# SCH.net
KiCad netlist of a schematic drawn in EasyEDA Pro
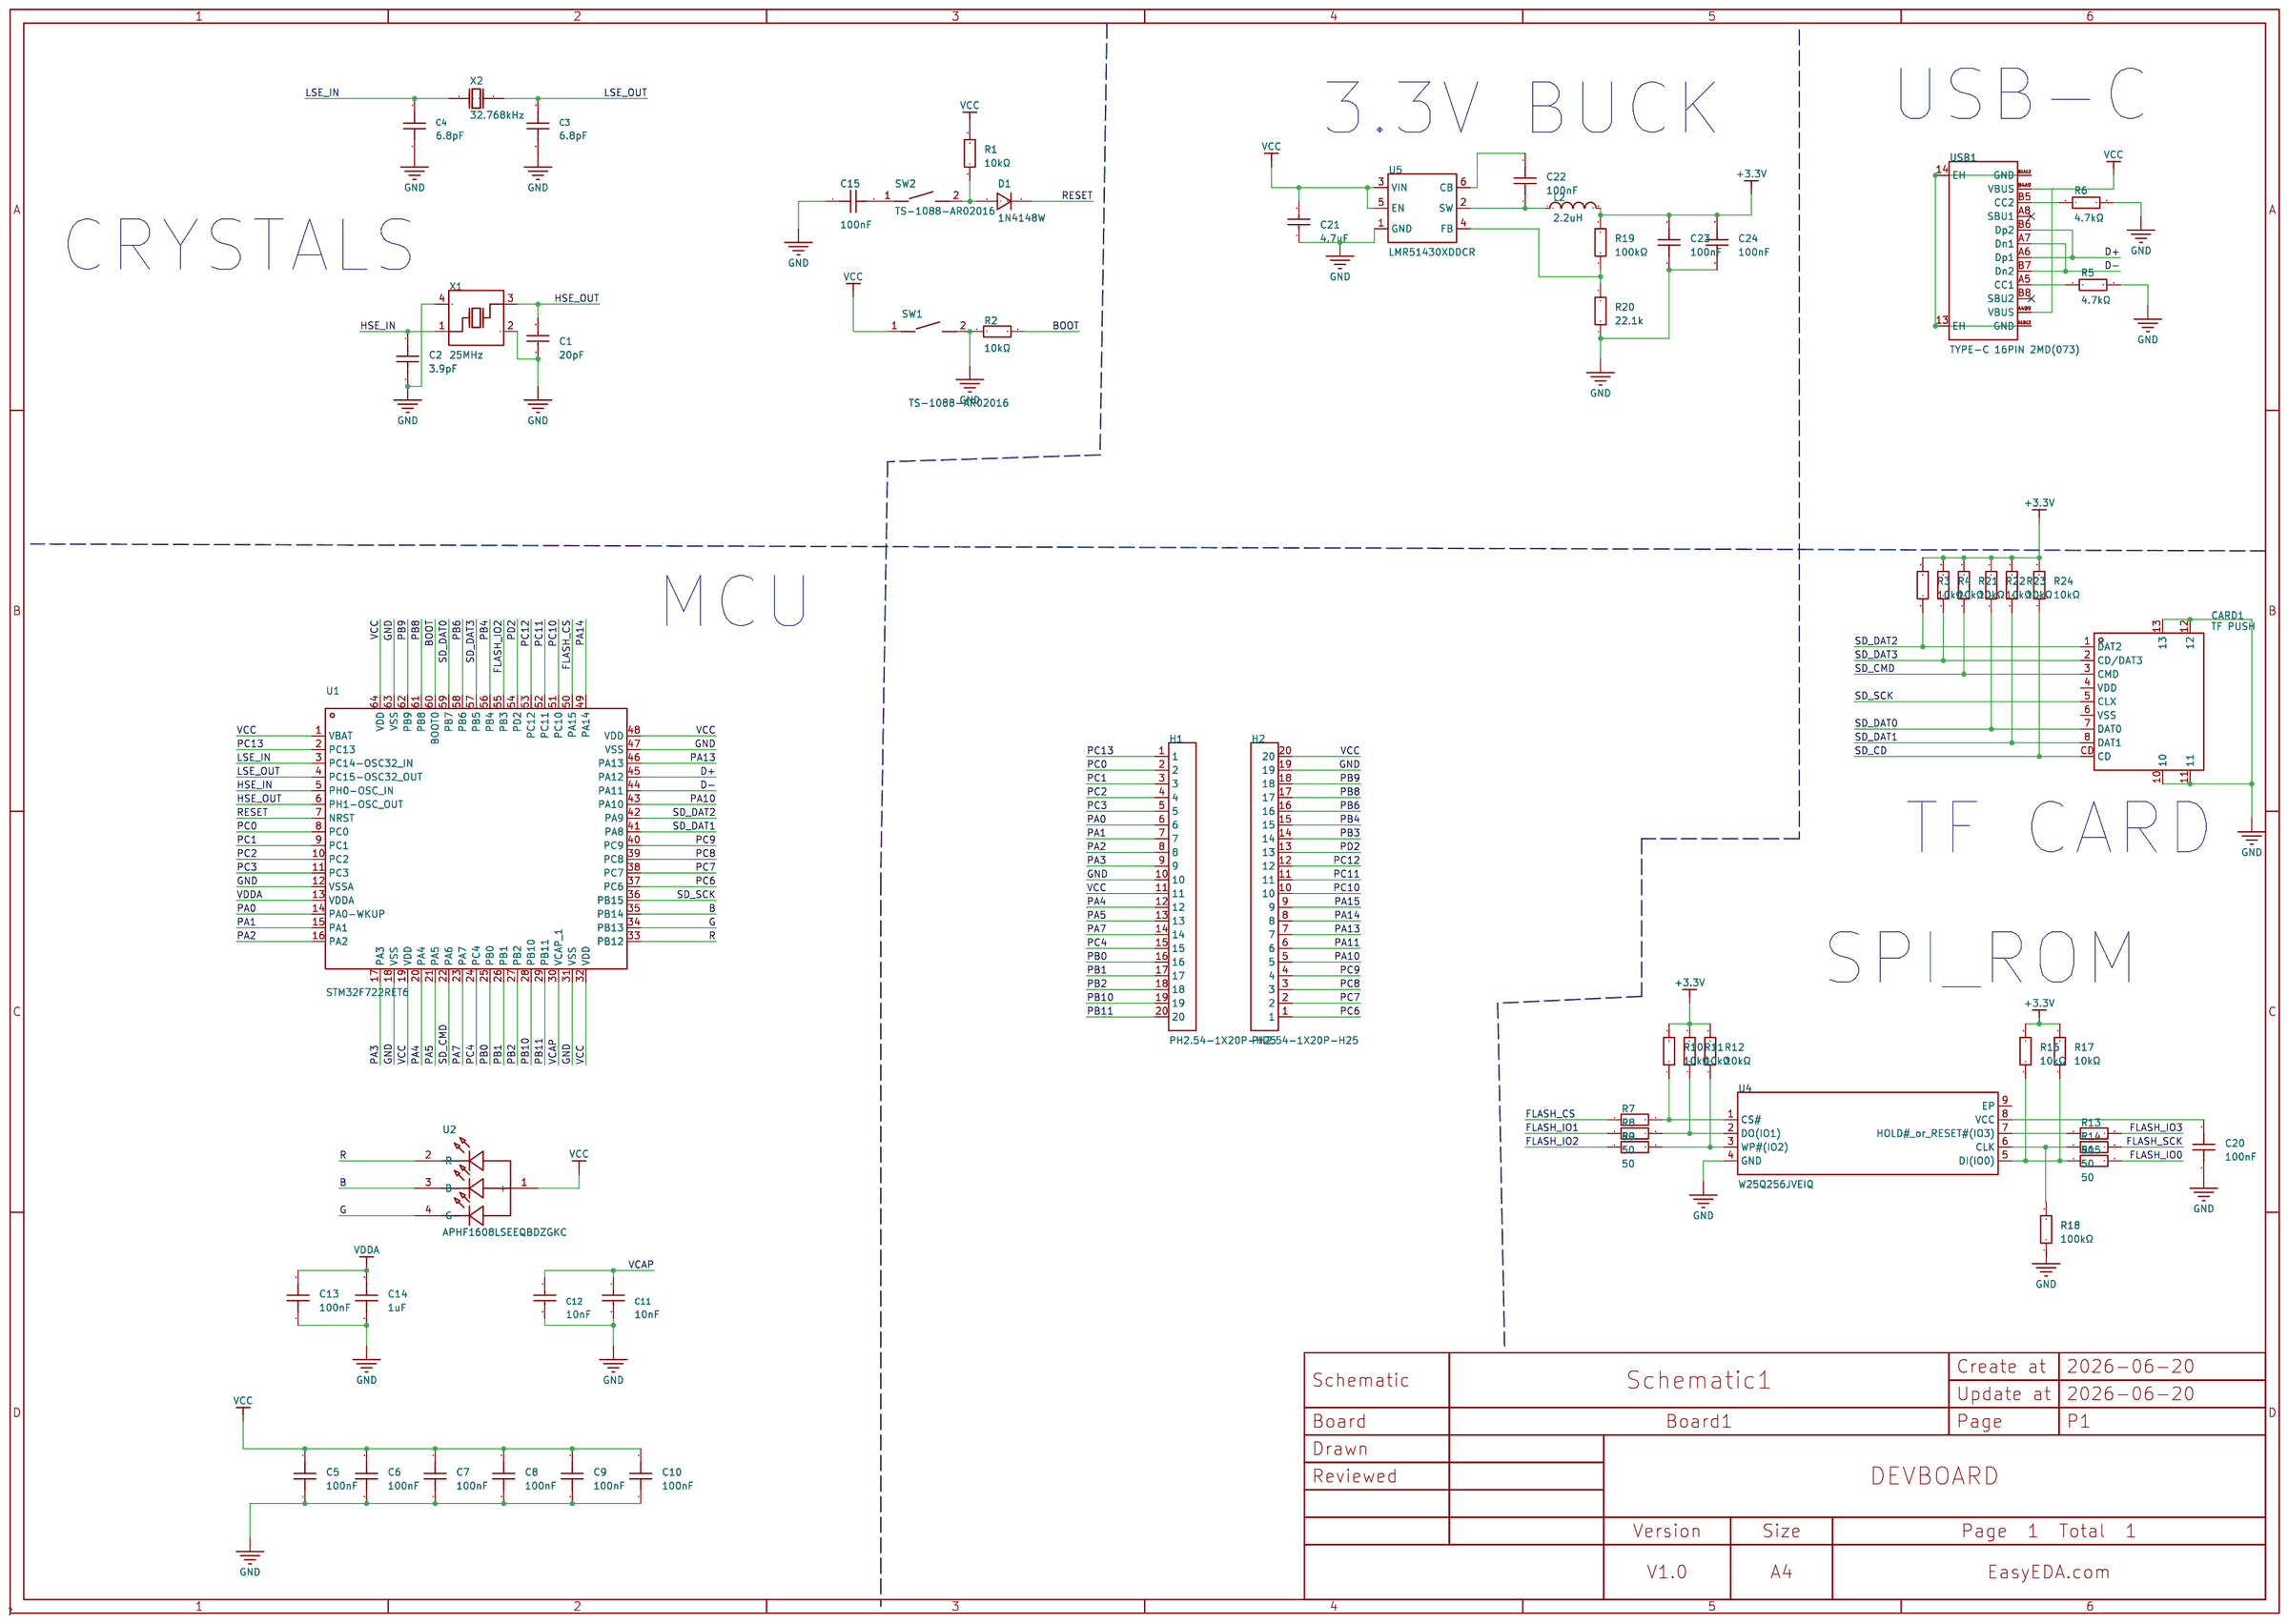
[diagram p0: schematic sheet]

(export (version "E")
  (design (tool "Eeschema 10.0.6"))
  (components
    (comp (ref "C1")
      (value "20pF")
      (footprint "easyedapro:C0603")
      (description "Capacitance:20pF Tolerance:±5% Tolerance:±5% Voltage Rating:50V Temperature Coefficient:C0G")
      (fields
        (field (name "Manufacturer Part") "CL10C200JB8NNNC")
        (field (name "Manufacturer") "SAMSUNG(三星)")
      )
      (libsource (lib "easyedapro") (part "CL10C200JB8NNNC"))
    )
    (comp (ref "C2")
      (value "3.9pF")
      (footprint "easyedapro:C0603")
      (libsource (lib "easyedapro") (part "CAP"))
    )
    (comp (ref "C3")
      (value "6.8pF")
      (footprint "easyedapro:C0603")
      (fields (field (name "Manufacturer") "SAMSUNG(三星)"))
      (libsource (lib "easyedapro") (part "6.8PF"))
    )
    (comp (ref "C4")
      (value "6.8pF")
      (footprint "easyedapro:C0603")
      (fields (field (name "Manufacturer") "SAMSUNG(三星)"))
      (libsource (lib "easyedapro") (part "6.8PF"))
    )
    (comp (ref "C5")
      (value "100nF")
      (footprint "easyedapro:C0603")
      (description "Capacitance:100nF Tolerance:±10% Tolerance:±10% Voltage Rating:50V Temperature Coefficient:X7R")
      (fields
        (field (name "Manufacturer Part") "CC0603KRX7R9BB104")
        (field (name "Manufacturer") "YAGEO(国巨)")
      )
      (libsource (lib "easyedapro") (part "CC0603KRX7R9BB104"))
    )
    (comp (ref "C6")
      (value "100nF")
      (footprint "easyedapro:C0603")
      (description "Capacitance:100nF Tolerance:±10% Tolerance:±10% Voltage Rating:50V Temperature Coefficient:X7R")
      (fields
        (field (name "Manufacturer Part") "CC0603KRX7R9BB104")
        (field (name "Manufacturer") "YAGEO(国巨)")
      )
      (libsource (lib "easyedapro") (part "CC0603KRX7R9BB104"))
    )
    (comp (ref "C7")
      (value "100nF")
      (footprint "easyedapro:C0603")
      (description "Capacitance:100nF Tolerance:±10% Tolerance:±10% Voltage Rating:50V Temperature Coefficient:X7R")
      (fields
        (field (name "Manufacturer Part") "CC0603KRX7R9BB104")
        (field (name "Manufacturer") "YAGEO(国巨)")
      )
      (libsource (lib "easyedapro") (part "CC0603KRX7R9BB104"))
    )
    (comp (ref "C8")
      (value "100nF")
      (footprint "easyedapro:C0603")
      (description "Capacitance:100nF Tolerance:±10% Tolerance:±10% Voltage Rating:50V Temperature Coefficient:X7R")
      (fields
        (field (name "Manufacturer Part") "CC0603KRX7R9BB104")
        (field (name "Manufacturer") "YAGEO(国巨)")
      )
      (libsource (lib "easyedapro") (part "CC0603KRX7R9BB104"))
    )
    (comp (ref "C9")
      (value "100nF")
      (footprint "easyedapro:C0603")
      (description "Capacitance:100nF Tolerance:±10% Tolerance:±10% Voltage Rating:50V Temperature Coefficient:X7R")
      (fields
        (field (name "Manufacturer Part") "CC0603KRX7R9BB104")
        (field (name "Manufacturer") "YAGEO(国巨)")
      )
      (libsource (lib "easyedapro") (part "CC0603KRX7R9BB104"))
    )
    (comp (ref "C10")
      (value "100nF")
      (footprint "easyedapro:C0603")
      (description "Capacitance:100nF Tolerance:±10% Tolerance:±10% Voltage Rating:50V Temperature Coefficient:X7R")
      (fields
        (field (name "Manufacturer Part") "CC0603KRX7R9BB104")
        (field (name "Manufacturer") "YAGEO(国巨)")
      )
      (libsource (lib "easyedapro") (part "CC0603KRX7R9BB104"))
    )
    (comp (ref "C11")
      (value "10nF")
      (footprint "easyedapro:C0402")
      (description "Capacitance:10nF Tolerance:±10% Tolerance:±10% Voltage Rating:50V Temperature Coefficient:X7R")
      (fields (field (name "Manufacturer Part") "0402B103K500NT") (field (name "Manufacturer") "FH(风华)"))
      (libsource (lib "easyedapro") (part "0402B103K500NT"))
    )
    (comp (ref "C12")
      (value "10nF")
      (footprint "easyedapro:C0402")
      (description "Capacitance:10nF Tolerance:±10% Tolerance:±10% Voltage Rating:50V Temperature Coefficient:X7R")
      (fields (field (name "Manufacturer Part") "0402B103K500NT") (field (name "Manufacturer") "FH(风华)"))
      (libsource (lib "easyedapro") (part "0402B103K500NT"))
    )
    (comp (ref "C13")
      (value "100nF")
      (footprint "easyedapro:C0603")
      (description "Capacitance:100nF Tolerance:±10% Tolerance:±10% Voltage Rating:50V Temperature Coefficient:X7R")
      (fields
        (field (name "Manufacturer Part") "CC0603KRX7R9BB104")
        (field (name "Manufacturer") "YAGEO(国巨)")
      )
      (libsource (lib "easyedapro") (part "CC0603KRX7R9BB104"))
    )
    (comp (ref "C14")
      (value "1uF")
      (footprint "easyedapro:C0603")
      (description "Capacitance:1uF Tolerance:±10% Tolerance:±10% Voltage Rating:50V Temperature Coefficient:X5R")
      (fields
        (field (name "Manufacturer Part") "CL10A105KB8NNNC")
        (field (name "Manufacturer") "SAMSUNG(三星)")
      )
      (libsource (lib "easyedapro") (part "CL10A105KB8NNNC"))
    )
    (comp (ref "C15")
      (value "100nF")
      (footprint "easyedapro:C0603")
      (description "Capacitance:100nF Tolerance:±10% Tolerance:±10% Voltage Rating:50V Temperature Coefficient:X7R")
      (fields
        (field (name "Manufacturer Part") "CC0603KRX7R9BB104")
        (field (name "Manufacturer") "YAGEO(国巨)")
      )
      (libsource (lib "easyedapro") (part "CC0603KRX7R9BB104"))
    )
    (comp (ref "C20")
      (value "100nF")
      (footprint "easyedapro:C0603")
      (description "Capacitance:100nF Tolerance:±10% Tolerance:±10% Voltage Rating:50V Temperature Coefficient:X7R")
      (fields
        (field (name "Manufacturer Part") "CC0603KRX7R9BB104")
        (field (name "Manufacturer") "YAGEO(国巨)")
      )
      (libsource (lib "easyedapro") (part "CC0603KRX7R9BB104"))
    )
    (comp (ref "C21")
      (value "4.7uF")
      (footprint "easyedapro:C0402")
      (description "Capacitance:4.7uF Tolerance:±10% Tolerance:±10% Voltage Rating:10V Temperature Coefficient:X5R")
      (fields
        (field (name "Manufacturer Part") "GRM155R61A475KEAAD")
        (field (name "Manufacturer") "muRata(村田)")
      )
      (libsource (lib "easyedapro") (part "GRM155R61A475KEAAD"))
    )
    (comp (ref "C22")
      (value "100nF")
      (footprint "easyedapro:C0603")
      (description "Capacitance:100nF Tolerance:±10% Tolerance:±10% Voltage Rating:50V Temperature Coefficient:X7R")
      (fields
        (field (name "Manufacturer Part") "CC0603KRX7R9BB104")
        (field (name "Manufacturer") "YAGEO(国巨)")
      )
      (libsource (lib "easyedapro") (part "CC0603KRX7R9BB104"))
    )
    (comp (ref "C23")
      (value "100nF")
      (footprint "easyedapro:C0603")
      (description "Capacitance:100nF Tolerance:±10% Tolerance:±10% Voltage Rating:50V Temperature Coefficient:X7R")
      (fields
        (field (name "Manufacturer Part") "CC0603KRX7R9BB104")
        (field (name "Manufacturer") "YAGEO(国巨)")
      )
      (libsource (lib "easyedapro") (part "CC0603KRX7R9BB104"))
    )
    (comp (ref "C24")
      (value "100nF")
      (footprint "easyedapro:C0603")
      (description "Capacitance:100nF Tolerance:±10% Tolerance:±10% Voltage Rating:50V Temperature Coefficient:X7R")
      (fields
        (field (name "Manufacturer Part") "CC0603KRX7R9BB104")
        (field (name "Manufacturer") "YAGEO(国巨)")
      )
      (libsource (lib "easyedapro") (part "CC0603KRX7R9BB104"))
    )
    (comp (ref "CARD1")
      (value "TF PUSH")
      (footprint "easyedapro:TF-SMD_TF-PUSH")
      (fields (field (name "Manufacturer") "SHOU HAN(首韩)"))
      (libsource (lib "easyedapro") (part "TF PUSH"))
    )
    (comp (ref "D1")
      (value "1N4148W")
      (footprint "easyedapro:SOD-123_L2.8-W1.8-LS3.7-RD")
      (fields (field (name "Manufacturer") "SMC(桑德斯)"))
      (libsource (lib "easyedapro") (part "1N4148W_C176288"))
    )
    (comp (ref "H1")
      (value "PH2.54-1X20P-H25")
      (footprint "easyedapro:HDR-TH_20P-P2.54-V-M_4")
      (fields (field (name "Manufacturer") "JXTCONN(聚兴泰)"))
      (libsource (lib "easyedapro") (part "PH2.54-1X20P-H25"))
    )
    (comp (ref "H2")
      (value "PH2.54-1X20P-H25")
      (footprint "easyedapro:HDR-TH_20P-P2.54-V-M_4")
      (fields (field (name "Manufacturer") "JXTCONN(聚兴泰)"))
      (libsource (lib "easyedapro") (part "PH2.54-1X20P-H25"))
    )
    (comp (ref "L2")
      (value "2.2uH")
      (footprint "easyedapro:IND-SMD_L4.0-W4.0_LQH44PN2R2MP0L")
      (fields
        (field (name "Manufacturer Part") "SMNR4020-2.2UH")
        (field (name "Manufacturer") "SXN(顺翔诺)")
        (field (name "Tolerance") "±20%")
      )
      (libsource (lib "easyedapro") (part "SMNR4020-2.2UH"))
    )
    (comp (ref "R1")
      (value "10kΩ")
      (footprint "easyedapro:R0603")
      (fields
        (field (name "Manufacturer Part") "RC0603FR-0710KL")
        (field (name "Manufacturer") "YAGEO(国巨)")
        (field (name "Tolerance") "±1%")
      )
      (libsource (lib "easyedapro") (part "RC0603FR-0710KL"))
    )
    (comp (ref "R2")
      (value "10kΩ")
      (footprint "easyedapro:R0603")
      (fields
        (field (name "Manufacturer Part") "RC0603FR-0710KL")
        (field (name "Manufacturer") "YAGEO(国巨)")
        (field (name "Tolerance") "±1%")
      )
      (libsource (lib "easyedapro") (part "RC0603FR-0710KL"))
    )
    (comp (ref "R3")
      (value "10kΩ")
      (footprint "easyedapro:R0603")
      (fields
        (field (name "Manufacturer Part") "RC0603FR-0710KL")
        (field (name "Manufacturer") "YAGEO(国巨)")
        (field (name "Tolerance") "±1%")
      )
      (libsource (lib "easyedapro") (part "RC0603FR-0710KL"))
    )
    (comp (ref "R4")
      (value "10kΩ")
      (footprint "easyedapro:R0603")
      (fields
        (field (name "Manufacturer Part") "RC0603FR-0710KL")
        (field (name "Manufacturer") "YAGEO(国巨)")
        (field (name "Tolerance") "±1%")
      )
      (libsource (lib "easyedapro") (part "RC0603FR-0710KL"))
    )
    (comp (ref "R5")
      (value "4.7kΩ")
      (footprint "easyedapro:R0603")
      (fields
        (field (name "Manufacturer Part") "0603WAF4701T5E")
        (field (name "Manufacturer") "UNI-ROYAL(厚声)")
        (field (name "Tolerance") "±1%")
      )
      (libsource (lib "easyedapro") (part "0603WAF4701T5E"))
    )
    (comp (ref "R6")
      (value "4.7kΩ")
      (footprint "easyedapro:R0603")
      (fields
        (field (name "Manufacturer Part") "0603WAF4701T5E")
        (field (name "Manufacturer") "UNI-ROYAL(厚声)")
        (field (name "Tolerance") "±1%")
      )
      (libsource (lib "easyedapro") (part "0603WAF4701T5E"))
    )
    (comp (ref "R7") (value "50") (footprint "easyedapro:R0603") (libsource (lib "easyedapro") (part "Res")))
    (comp (ref "R8") (value "50") (footprint "easyedapro:R0603") (libsource (lib "easyedapro") (part "Res")))
    (comp (ref "R9") (value "50") (footprint "easyedapro:R0603") (libsource (lib "easyedapro") (part "Res")))
    (comp (ref "R10")
      (value "10kΩ")
      (footprint "easyedapro:R0603")
      (fields
        (field (name "Manufacturer Part") "RC0603FR-0710KL")
        (field (name "Manufacturer") "YAGEO(国巨)")
        (field (name "Tolerance") "±1%")
      )
      (libsource (lib "easyedapro") (part "RC0603FR-0710KL"))
    )
    (comp (ref "R11")
      (value "10kΩ")
      (footprint "easyedapro:R0603")
      (fields
        (field (name "Manufacturer Part") "RC0603FR-0710KL")
        (field (name "Manufacturer") "YAGEO(国巨)")
        (field (name "Tolerance") "±1%")
      )
      (libsource (lib "easyedapro") (part "RC0603FR-0710KL"))
    )
    (comp (ref "R12")
      (value "10kΩ")
      (footprint "easyedapro:R0603")
      (fields
        (field (name "Manufacturer Part") "RC0603FR-0710KL")
        (field (name "Manufacturer") "YAGEO(国巨)")
        (field (name "Tolerance") "±1%")
      )
      (libsource (lib "easyedapro") (part "RC0603FR-0710KL"))
    )
    (comp (ref "R13") (value "50") (footprint "easyedapro:R0603") (libsource (lib "easyedapro") (part "Res")))
    (comp (ref "R14") (value "50") (footprint "easyedapro:R0603") (libsource (lib "easyedapro") (part "Res")))
    (comp (ref "R15") (value "50") (footprint "easyedapro:R0603") (libsource (lib "easyedapro") (part "Res")))
    (comp (ref "R16")
      (value "10kΩ")
      (footprint "easyedapro:R0603")
      (fields
        (field (name "Manufacturer Part") "RC0603FR-0710KL")
        (field (name "Manufacturer") "YAGEO(国巨)")
        (field (name "Tolerance") "±1%")
      )
      (libsource (lib "easyedapro") (part "RC0603FR-0710KL"))
    )
    (comp (ref "R17")
      (value "10kΩ")
      (footprint "easyedapro:R0603")
      (fields
        (field (name "Manufacturer Part") "RC0603FR-0710KL")
        (field (name "Manufacturer") "YAGEO(国巨)")
        (field (name "Tolerance") "±1%")
      )
      (libsource (lib "easyedapro") (part "RC0603FR-0710KL"))
    )
    (comp (ref "R18")
      (value "100kΩ")
      (fields
        (field (name "Manufacturer Part") "0603WAF1003T5E")
        (field (name "Manufacturer") "UNI-ROYAL(厚声)")
        (field (name "Tolerance") "±1%")
      )
      (libsource (lib "easyedapro") (part "0603WAF1003T5E"))
    )
    (comp (ref "R19")
      (value "100kΩ")
      (fields
        (field (name "Manufacturer Part") "0603WAF1003T5E")
        (field (name "Manufacturer") "UNI-ROYAL(厚声)")
        (field (name "Tolerance") "±1%")
      )
      (libsource (lib "easyedapro") (part "0603WAF1003T5E"))
    )
    (comp (ref "R20")
      (value "22.1k")
      (footprint "easyedapro:R0603")
      (fields
        (field (name "Manufacturer Part") "RMC060322.1K1%N")
        (field (name "Manufacturer") "Tyohm(幸亚电阻)")
        (field (name "Tolerance") "±1%")
      )
      (libsource (lib "easyedapro") (part "Res"))
    )
    (comp (ref "R21")
      (value "10kΩ")
      (footprint "easyedapro:R0603")
      (fields
        (field (name "Manufacturer Part") "RC0603FR-0710KL")
        (field (name "Manufacturer") "YAGEO(国巨)")
        (field (name "Tolerance") "±1%")
      )
      (libsource (lib "easyedapro") (part "RC0603FR-0710KL"))
    )
    (comp (ref "R22")
      (value "10kΩ")
      (footprint "easyedapro:R0603")
      (fields
        (field (name "Manufacturer Part") "RC0603FR-0710KL")
        (field (name "Manufacturer") "YAGEO(国巨)")
        (field (name "Tolerance") "±1%")
      )
      (libsource (lib "easyedapro") (part "RC0603FR-0710KL"))
    )
    (comp (ref "R23")
      (value "10kΩ")
      (footprint "easyedapro:R0603")
      (fields
        (field (name "Manufacturer Part") "RC0603FR-0710KL")
        (field (name "Manufacturer") "YAGEO(国巨)")
        (field (name "Tolerance") "±1%")
      )
      (libsource (lib "easyedapro") (part "RC0603FR-0710KL"))
    )
    (comp (ref "R24")
      (value "10kΩ")
      (footprint "easyedapro:R0603")
      (fields
        (field (name "Manufacturer Part") "RC0603FR-0710KL")
        (field (name "Manufacturer") "YAGEO(国巨)")
        (field (name "Tolerance") "±1%")
      )
      (libsource (lib "easyedapro") (part "RC0603FR-0710KL"))
    )
    (comp (ref "SW1")
      (value "TS-1088-AR02016")
      (footprint "easyedapro:SW-SMD_L3.9-W3.0-P4.45")
      (fields (field (name "Manufacturer") "XUNPU(讯普)"))
      (libsource (lib "easyedapro") (part "TS-1088-AR02016"))
    )
    (comp (ref "SW2")
      (value "TS-1088-AR02016")
      (footprint "easyedapro:SW-SMD_L3.9-W3.0-P4.45")
      (fields (field (name "Manufacturer") "XUNPU(讯普)"))
      (libsource (lib "easyedapro") (part "TS-1088-AR02016"))
    )
    (comp (ref "U1")
      (value "STM32F722RET6")
      (footprint "easyedapro:LQFP-64_L10.0-W10.0-P0.50-LS12.0-BL")
      (fields (field (name "Manufacturer") "ST(意法半导体)"))
      (libsource (lib "easyedapro") (part "STM32F722RET6"))
    )
    (comp (ref "U2")
      (value "APHF1608LSEEQBDZGKC")
      (footprint "easyedapro:LED-SMD_4P-L1.6-W0.8_APHF1608LSEEQBDZGKC")
      (fields (field (name "Manufacturer") "Kingbright"))
      (libsource (lib "easyedapro") (part "APHF1608LSEEQBDZGKC"))
    )
    (comp (ref "U4")
      (value "W25Q256JVEIQ")
      (footprint "easyedapro:WSON-8_L8.0-W6.10-P1.27-BL-EP")
      (fields (field (name "Manufacturer") "Winbond(华邦)"))
      (libsource (lib "easyedapro") (part "W25Q256JVEIQTR"))
    )
    (comp (ref "U5")
      (value "LMR51430XDDCR")
      (footprint "easyedapro:SOT-23-6_L2.9-W1.6-P0.95-LS2.8-BL")
      (fields (field (name "Manufacturer") "TI(德州仪器)"))
      (libsource (lib "easyedapro") (part "LMR51430XDDCR"))
    )
    (comp (ref "USB1")
      (value "TYPE-C 16PIN 2MD(073)")
      (footprint "easyedapro:USB-C-SMD_TYPE-C-16PIN-2MD-073")
      (fields (field (name "Manufacturer") "SHOU HAN(首韩)"))
      (libsource (lib "easyedapro") (part "TYPE-C 16PIN 2MD(073)"))
    )
    (comp (ref "X1")
      (value "25MHz")
      (footprint "easyedapro:CRYSTAL-SMD_4P-L3.2-W2.5-BL")
      (fields (field (name "Manufacturer Part") "X322525MOB4SI") (field (name "Manufacturer") "YXC(扬兴晶振)"))
      (libsource (lib "easyedapro") (part "X322525MOB4SI"))
    )
    (comp (ref "X2")
      (value "32.768kHz")
      (footprint "easyedapro:OSC-SMD_2P-L1.6-W1.0")
      (fields (field (name "Manufacturer Part") "ABS05-32.768kHz-T") (field (name "Manufacturer") "ABRACON"))
      (libsource (lib "easyedapro") (part "ABS05-32.768KHZ-T"))
    )
  )
  (nets
    (net (code "1") (name "+3.3V") (class "Default")
      (node (ref "C23") (pin "2") (pinfunction "2_2") (pintype "unspecified"))
      (node (ref "C24") (pin "2") (pinfunction "2_2") (pintype "unspecified"))
      (node (ref "L2") (pin "2") (pinfunction "2_2") (pintype "input"))
      (node (ref "R10") (pin "2") (pinfunction "2_2") (pintype "input"))
      (node (ref "R11") (pin "2") (pinfunction "2_2") (pintype "input"))
      (node (ref "R12") (pin "2") (pinfunction "2_2") (pintype "input"))
      (node (ref "R16") (pin "2") (pinfunction "2_2") (pintype "input"))
      (node (ref "R17") (pin "2") (pinfunction "2_2") (pintype "input"))
      (node (ref "R19") (pin "2") (pinfunction "2_2") (pintype "input"))
      (node (ref "R21") (pin "2") (pinfunction "2_2") (pintype "input"))
      (node (ref "R22") (pin "2") (pinfunction "2_2") (pintype "input"))
      (node (ref "R23") (pin "2") (pinfunction "2_2") (pintype "input"))
      (node (ref "R24") (pin "2") (pinfunction "2_2") (pintype "input"))
      (node (ref "R3") (pin "2") (pinfunction "2_2") (pintype "input"))
      (node (ref "R4") (pin "2") (pinfunction "2_2") (pintype "input"))
    )
    (net (code "2") (name "/B") (class "Default")
      (node (ref "U1") (pin "35") (pinfunction "PB14_35") (pintype "unspecified"))
      (node (ref "U2") (pin "3") (pinfunction "B-_3") (pintype "unspecified"))
    )
    (net (code "3") (name "/BOOT") (class "Default")
      (node (ref "R2") (pin "1") (pinfunction "1_1") (pintype "input"))
      (node (ref "U1") (pin "60") (pinfunction "BOOT0_60") (pintype "unspecified"))
    )
    (net (code "4") (name "/D+") (class "Default")
      (node (ref "U1") (pin "45") (pinfunction "PA12_45") (pintype "unspecified"))
      (node (ref "USB1") (pin "A6") (pinfunction "Dp1_A6") (pintype "unspecified"))
      (node (ref "USB1") (pin "B6") (pinfunction "Dp2_B6") (pintype "unspecified"))
    )
    (net (code "5") (name "/D-") (class "Default")
      (node (ref "U1") (pin "44") (pinfunction "PA11_44") (pintype "unspecified"))
      (node (ref "USB1") (pin "A7") (pinfunction "Dn1_A7") (pintype "unspecified"))
      (node (ref "USB1") (pin "B7") (pinfunction "Dn2_B7") (pintype "unspecified"))
    )
    (net (code "6") (name "/FLASH_CS") (class "Default")
      (node (ref "R7") (pin "1") (pinfunction "1_1") (pintype "input"))
      (node (ref "U1") (pin "50") (pinfunction "PA15_50") (pintype "unspecified"))
    )
    (net (code "7") (name "/FLASH_IO0") (class "Default")
      (node (ref "R15") (pin "2") (pinfunction "2_2") (pintype "input"))
    )
    (net (code "8") (name "/FLASH_IO1") (class "Default")
      (node (ref "R8") (pin "1") (pinfunction "1_1") (pintype "input"))
    )
    (net (code "9") (name "/FLASH_IO2") (class "Default")
      (node (ref "R9") (pin "1") (pinfunction "1_1") (pintype "input"))
      (node (ref "U1") (pin "55") (pinfunction "PB3_55") (pintype "unspecified"))
    )
    (net (code "10") (name "/FLASH_IO3") (class "Default")
      (node (ref "R13") (pin "2") (pinfunction "2_2") (pintype "input"))
    )
    (net (code "11") (name "/FLASH_SCK") (class "Default")
      (node (ref "R14") (pin "2") (pinfunction "2_2") (pintype "input"))
    )
    (net (code "12") (name "/G") (class "Default")
      (node (ref "U1") (pin "34") (pinfunction "PB13_34") (pintype "unspecified"))
      (node (ref "U2") (pin "4") (pinfunction "G-_4") (pintype "unspecified"))
    )
    (net (code "13") (name "/HSE_IN") (class "Default")
      (node (ref "C2") (pin "1") (pinfunction "1_1") (pintype "input"))
      (node (ref "U1") (pin "5") (pinfunction "PH0-OSC_IN_5") (pintype "unspecified"))
      (node (ref "X1") (pin "1") (pinfunction "OSC1_1") (pintype "unspecified"))
    )
    (net (code "14") (name "/HSE_OUT") (class "Default")
      (node (ref "C1") (pin "2") (pinfunction "2_2") (pintype "input"))
      (node (ref "U1") (pin "6") (pinfunction "PH1-OSC_OUT_6") (pintype "unspecified"))
      (node (ref "X1") (pin "3") (pinfunction "OSC2_3") (pintype "unspecified"))
    )
    (net (code "15") (name "/LSE_IN") (class "Default")
      (node (ref "C4") (pin "1") (pinfunction "1_1") (pintype "input"))
      (node (ref "U1") (pin "3") (pinfunction "PC14-OSC32_IN_3") (pintype "unspecified"))
      (node (ref "X2") (pin "1") (pinfunction "OSC1_1") (pintype "input"))
    )
    (net (code "16") (name "/LSE_OUT") (class "Default")
      (node (ref "C3") (pin "1") (pinfunction "1_1") (pintype "input"))
      (node (ref "U1") (pin "4") (pinfunction "PC15-OSC32_OUT_4") (pintype "unspecified"))
      (node (ref "X2") (pin "2") (pinfunction "OSC2_2") (pintype "input"))
    )
    (net (code "17") (name "/PA0") (class "Default")
      (node (ref "H1") (pin "6") (pinfunction "6_6") (pintype "unspecified"))
      (node (ref "U1") (pin "14") (pinfunction "PA0-WKUP_14") (pintype "unspecified"))
    )
    (net (code "18") (name "/PA1") (class "Default")
      (node (ref "H1") (pin "7") (pinfunction "7_7") (pintype "unspecified"))
      (node (ref "U1") (pin "15") (pinfunction "PA1_15") (pintype "unspecified"))
    )
    (net (code "19") (name "/PA2") (class "Default")
      (node (ref "H1") (pin "8") (pinfunction "8_8") (pintype "unspecified"))
      (node (ref "U1") (pin "16") (pinfunction "PA2_16") (pintype "unspecified"))
    )
    (net (code "20") (name "/PA3") (class "Default")
      (node (ref "H1") (pin "9") (pinfunction "9_9") (pintype "unspecified"))
      (node (ref "U1") (pin "17") (pinfunction "PA3_17") (pintype "unspecified"))
    )
    (net (code "21") (name "/PA4") (class "Default")
      (node (ref "H1") (pin "12") (pinfunction "12_12") (pintype "unspecified"))
      (node (ref "U1") (pin "20") (pinfunction "PA4_20") (pintype "unspecified"))
    )
    (net (code "22") (name "/PA5") (class "Default")
      (node (ref "H1") (pin "13") (pinfunction "13_13") (pintype "unspecified"))
      (node (ref "U1") (pin "21") (pinfunction "PA5_21") (pintype "unspecified"))
    )
    (net (code "23") (name "/PA7") (class "Default")
      (node (ref "H1") (pin "14") (pinfunction "14_14") (pintype "unspecified"))
      (node (ref "U1") (pin "23") (pinfunction "PA7_23") (pintype "unspecified"))
    )
    (net (code "24") (name "/PA10") (class "Default")
      (node (ref "H2") (pin "5") (pinfunction "5_5") (pintype "unspecified"))
      (node (ref "U1") (pin "43") (pinfunction "PA10_43") (pintype "unspecified"))
    )
    (net (code "25") (name "/PA11") (class "Default")
      (node (ref "H2") (pin "6") (pinfunction "6_6") (pintype "unspecified"))
    )
    (net (code "26") (name "/PA13") (class "Default")
      (node (ref "H2") (pin "7") (pinfunction "7_7") (pintype "unspecified"))
      (node (ref "U1") (pin "46") (pinfunction "PA13_46") (pintype "unspecified"))
    )
    (net (code "27") (name "/PA14") (class "Default")
      (node (ref "H2") (pin "8") (pinfunction "8_8") (pintype "unspecified"))
      (node (ref "U1") (pin "49") (pinfunction "PA14_49") (pintype "unspecified"))
    )
    (net (code "28") (name "/PA15") (class "Default")
      (node (ref "H2") (pin "9") (pinfunction "9_9") (pintype "unspecified"))
    )
    (net (code "29") (name "/PB0") (class "Default")
      (node (ref "H1") (pin "16") (pinfunction "16_16") (pintype "unspecified"))
      (node (ref "U1") (pin "25") (pinfunction "PB0_25") (pintype "unspecified"))
    )
    (net (code "30") (name "/PB1") (class "Default")
      (node (ref "H1") (pin "17") (pinfunction "17_17") (pintype "unspecified"))
      (node (ref "U1") (pin "26") (pinfunction "PB1_26") (pintype "unspecified"))
    )
    (net (code "31") (name "/PB2") (class "Default")
      (node (ref "H1") (pin "18") (pinfunction "18_18") (pintype "unspecified"))
      (node (ref "U1") (pin "27") (pinfunction "PB2_27") (pintype "unspecified"))
    )
    (net (code "32") (name "/PB3") (class "Default")
      (node (ref "H2") (pin "14") (pinfunction "14_14") (pintype "unspecified"))
    )
    (net (code "33") (name "/PB4") (class "Default")
      (node (ref "H2") (pin "15") (pinfunction "15_15") (pintype "unspecified"))
      (node (ref "U1") (pin "56") (pinfunction "PB4_56") (pintype "unspecified"))
    )
    (net (code "34") (name "/PB6") (class "Default")
      (node (ref "H2") (pin "16") (pinfunction "16_16") (pintype "unspecified"))
      (node (ref "U1") (pin "58") (pinfunction "PB6_58") (pintype "unspecified"))
    )
    (net (code "35") (name "/PB8") (class "Default")
      (node (ref "H2") (pin "17") (pinfunction "17_17") (pintype "unspecified"))
      (node (ref "U1") (pin "61") (pinfunction "PB8_61") (pintype "unspecified"))
    )
    (net (code "36") (name "/PB9") (class "Default")
      (node (ref "H2") (pin "18") (pinfunction "18_18") (pintype "unspecified"))
      (node (ref "U1") (pin "62") (pinfunction "PB9_62") (pintype "unspecified"))
    )
    (net (code "37") (name "/PB10") (class "Default")
      (node (ref "H1") (pin "19") (pinfunction "19_19") (pintype "unspecified"))
      (node (ref "U1") (pin "28") (pinfunction "PB10_28") (pintype "unspecified"))
    )
    (net (code "38") (name "/PB11") (class "Default")
      (node (ref "H1") (pin "20") (pinfunction "20_20") (pintype "unspecified"))
      (node (ref "U1") (pin "29") (pinfunction "PB11_29") (pintype "unspecified"))
    )
    (net (code "39") (name "/PC0") (class "Default")
      (node (ref "H1") (pin "2") (pinfunction "2_2") (pintype "unspecified"))
      (node (ref "U1") (pin "8") (pinfunction "PC0_8") (pintype "unspecified"))
    )
    (net (code "40") (name "/PC1") (class "Default")
      (node (ref "H1") (pin "3") (pinfunction "3_3") (pintype "unspecified"))
      (node (ref "U1") (pin "9") (pinfunction "PC1_9") (pintype "unspecified"))
    )
    (net (code "41") (name "/PC2") (class "Default")
      (node (ref "H1") (pin "4") (pinfunction "4_4") (pintype "unspecified"))
      (node (ref "U1") (pin "10") (pinfunction "PC2_10") (pintype "unspecified"))
    )
    (net (code "42") (name "/PC3") (class "Default")
      (node (ref "H1") (pin "5") (pinfunction "5_5") (pintype "unspecified"))
      (node (ref "U1") (pin "11") (pinfunction "PC3_11") (pintype "unspecified"))
    )
    (net (code "43") (name "/PC4") (class "Default")
      (node (ref "H1") (pin "15") (pinfunction "15_15") (pintype "unspecified"))
      (node (ref "U1") (pin "24") (pinfunction "PC4_24") (pintype "unspecified"))
    )
    (net (code "44") (name "/PC6") (class "Default")
      (node (ref "H2") (pin "1") (pinfunction "1_1") (pintype "unspecified"))
      (node (ref "U1") (pin "37") (pinfunction "PC6_37") (pintype "unspecified"))
    )
    (net (code "45") (name "/PC7") (class "Default")
      (node (ref "H2") (pin "2") (pinfunction "2_2") (pintype "unspecified"))
      (node (ref "U1") (pin "38") (pinfunction "PC7_38") (pintype "unspecified"))
    )
    (net (code "46") (name "/PC8") (class "Default")
      (node (ref "H2") (pin "3") (pinfunction "3_3") (pintype "unspecified"))
      (node (ref "U1") (pin "39") (pinfunction "PC8_39") (pintype "unspecified"))
    )
    (net (code "47") (name "/PC9") (class "Default")
      (node (ref "H2") (pin "4") (pinfunction "4_4") (pintype "unspecified"))
      (node (ref "U1") (pin "40") (pinfunction "PC9_40") (pintype "unspecified"))
    )
    (net (code "48") (name "/PC10") (class "Default")
      (node (ref "H2") (pin "10") (pinfunction "10_10") (pintype "unspecified"))
      (node (ref "U1") (pin "51") (pinfunction "PC10_51") (pintype "unspecified"))
    )
    (net (code "49") (name "/PC11") (class "Default")
      (node (ref "H2") (pin "11") (pinfunction "11_11") (pintype "unspecified"))
      (node (ref "U1") (pin "52") (pinfunction "PC11_52") (pintype "unspecified"))
    )
    (net (code "50") (name "/PC12") (class "Default")
      (node (ref "H2") (pin "12") (pinfunction "12_12") (pintype "unspecified"))
      (node (ref "U1") (pin "53") (pinfunction "PC12_53") (pintype "unspecified"))
    )
    (net (code "51") (name "/PC13") (class "Default")
      (node (ref "H1") (pin "1") (pinfunction "1_1") (pintype "unspecified"))
      (node (ref "U1") (pin "2") (pinfunction "PC13_2") (pintype "unspecified"))
    )
    (net (code "52") (name "/PD2") (class "Default")
      (node (ref "H2") (pin "13") (pinfunction "13_13") (pintype "unspecified"))
      (node (ref "U1") (pin "54") (pinfunction "PD2_54") (pintype "unspecified"))
    )
    (net (code "53") (name "/R") (class "Default")
      (node (ref "U1") (pin "33") (pinfunction "PB12_33") (pintype "unspecified"))
      (node (ref "U2") (pin "2") (pinfunction "R-_2") (pintype "unspecified"))
    )
    (net (code "54") (name "/RESET") (class "Default")
      (node (ref "D1") (pin "1") (pinfunction "C_1") (pintype "input"))
      (node (ref "U1") (pin "7") (pinfunction "NRST_7") (pintype "unspecified"))
    )
    (net (code "55") (name "/SD_CD") (class "Default")
      (node (ref "CARD1") (pin "CD") (pinfunction "CD_CD") (pintype "unspecified"))
      (node (ref "R24") (pin "1") (pinfunction "1_1") (pintype "input"))
    )
    (net (code "56") (name "/SD_CMD") (class "Default")
      (node (ref "CARD1") (pin "3") (pinfunction "CMD_3") (pintype "unspecified"))
      (node (ref "R21") (pin "1") (pinfunction "1_1") (pintype "input"))
      (node (ref "U1") (pin "22") (pinfunction "PA6_22") (pintype "unspecified"))
    )
    (net (code "57") (name "/SD_DAT0") (class "Default")
      (node (ref "CARD1") (pin "7") (pinfunction "DAT0_7") (pintype "unspecified"))
      (node (ref "R22") (pin "1") (pinfunction "1_1") (pintype "input"))
      (node (ref "U1") (pin "59") (pinfunction "PB7_59") (pintype "unspecified"))
    )
    (net (code "58") (name "/SD_DAT1") (class "Default")
      (node (ref "CARD1") (pin "8") (pinfunction "DAT1_8") (pintype "unspecified"))
      (node (ref "R23") (pin "1") (pinfunction "1_1") (pintype "input"))
      (node (ref "U1") (pin "41") (pinfunction "PA8_41") (pintype "unspecified"))
    )
    (net (code "59") (name "/SD_DAT2") (class "Default")
      (node (ref "CARD1") (pin "1") (pinfunction "DAT2_1") (pintype "unspecified"))
      (node (ref "R3") (pin "1") (pinfunction "1_1") (pintype "input"))
      (node (ref "U1") (pin "42") (pinfunction "PA9_42") (pintype "unspecified"))
    )
    (net (code "60") (name "/SD_DAT3") (class "Default")
      (node (ref "CARD1") (pin "2") (pinfunction "CD/DAT3_2") (pintype "unspecified"))
      (node (ref "R4") (pin "1") (pinfunction "1_1") (pintype "input"))
      (node (ref "U1") (pin "57") (pinfunction "PB5_57") (pintype "unspecified"))
    )
    (net (code "61") (name "/SD_SCK") (class "Default")
      (node (ref "CARD1") (pin "5") (pinfunction "CLX_5") (pintype "unspecified"))
      (node (ref "U1") (pin "36") (pinfunction "PB15_36") (pintype "unspecified"))
    )
    (net (code "62") (name "/VCAP") (class "Default")
      (node (ref "C11") (pin "2") (pinfunction "2_2") (pintype "input"))
      (node (ref "C12") (pin "2") (pinfunction "2_2") (pintype "input"))
      (node (ref "U1") (pin "30") (pinfunction "VCAP_1_30") (pintype "unspecified"))
    )
    (net (code "63") (name "GND") (class "Default")
      (node (ref "C1") (pin "1") (pinfunction "1_1") (pintype "input"))
      (node (ref "C10") (pin "1") (pinfunction "1_1") (pintype "unspecified"))
      (node (ref "C11") (pin "1") (pinfunction "1_1") (pintype "input"))
      (node (ref "C12") (pin "1") (pinfunction "1_1") (pintype "input"))
      (node (ref "C13") (pin "1") (pinfunction "1_1") (pintype "unspecified"))
      (node (ref "C14") (pin "1") (pinfunction "1_1") (pintype "unspecified"))
      (node (ref "C15") (pin "1") (pinfunction "1_1") (pintype "unspecified"))
      (node (ref "C2") (pin "2") (pinfunction "2_2") (pintype "input"))
      (node (ref "C20") (pin "1") (pinfunction "1_1") (pintype "unspecified"))
      (node (ref "C21") (pin "1") (pinfunction "1_1") (pintype "input"))
      (node (ref "C23") (pin "1") (pinfunction "1_1") (pintype "unspecified"))
      (node (ref "C24") (pin "1") (pinfunction "1_1") (pintype "unspecified"))
      (node (ref "C3") (pin "2") (pinfunction "2_2") (pintype "input"))
      (node (ref "C4") (pin "2") (pinfunction "2_2") (pintype "input"))
      (node (ref "C5") (pin "1") (pinfunction "1_1") (pintype "unspecified"))
      (node (ref "C6") (pin "1") (pinfunction "1_1") (pintype "unspecified"))
      (node (ref "C7") (pin "1") (pinfunction "1_1") (pintype "unspecified"))
      (node (ref "C8") (pin "1") (pinfunction "1_1") (pintype "unspecified"))
      (node (ref "C9") (pin "1") (pinfunction "1_1") (pintype "unspecified"))
      (node (ref "CARD1") (pin "10") (pinfunction "10_10") (pintype "unspecified"))
      (node (ref "CARD1") (pin "11") (pinfunction "11_11") (pintype "unspecified"))
      (node (ref "CARD1") (pin "12") (pinfunction "12_12") (pintype "unspecified"))
      (node (ref "CARD1") (pin "13") (pinfunction "13_13") (pintype "unspecified"))
      (node (ref "H1") (pin "10") (pinfunction "10_10") (pintype "unspecified"))
      (node (ref "H2") (pin "19") (pinfunction "19_19") (pintype "unspecified"))
      (node (ref "R18") (pin "1") (pinfunction "1_1") (pintype "input"))
      (node (ref "R2") (pin "2") (pinfunction "2_2") (pintype "input"))
      (node (ref "R20") (pin "1") (pinfunction "1_1") (pintype "input"))
      (node (ref "R5") (pin "2") (pinfunction "2_2") (pintype "input"))
      (node (ref "R6") (pin "2") (pinfunction "2_2") (pintype "input"))
      (node (ref "SW1") (pin "2") (pinfunction "2_2") (pintype "unspecified"))
      (node (ref "U1") (pin "12") (pinfunction "VSSA_12") (pintype "unspecified"))
      (node (ref "U1") (pin "18") (pinfunction "VSS_18") (pintype "unspecified"))
      (node (ref "U1") (pin "31") (pinfunction "VSS_31") (pintype "unspecified"))
      (node (ref "U1") (pin "47") (pinfunction "VSS_47") (pintype "unspecified"))
      (node (ref "U1") (pin "63") (pinfunction "VSS_63") (pintype "unspecified"))
      (node (ref "U4") (pin "4") (pinfunction "GND_4") (pintype "unspecified"))
      (node (ref "U5") (pin "1") (pinfunction "GND_1") (pintype "unspecified"))
      (node (ref "X1") (pin "2") (pinfunction "GND_2") (pintype "unspecified"))
      (node (ref "X1") (pin "4") (pinfunction "GND_4") (pintype "unspecified"))
    )
    (net (code "64") (name "Net-(C15-Pad2)") (class "Default")
      (node (ref "C15") (pin "2") (pinfunction "2_2") (pintype "unspecified"))
      (node (ref "SW2") (pin "1") (pinfunction "1_1") (pintype "unspecified"))
    )
    (net (code "65") (name "Net-(D1-A)") (class "Default")
      (node (ref "D1") (pin "2") (pinfunction "A_2") (pintype "input"))
      (node (ref "R1") (pin "1") (pinfunction "1_1") (pintype "input"))
      (node (ref "SW2") (pin "2") (pinfunction "2_2") (pintype "unspecified"))
    )
    (net (code "66") (name "Net-(U4-CLK)") (class "Default")
      (node (ref "R14") (pin "1") (pinfunction "1_1") (pintype "input"))
      (node (ref "R18") (pin "2") (pinfunction "2_2") (pintype "input"))
      (node (ref "U4") (pin "6") (pinfunction "CLK_6") (pintype "unspecified"))
    )
    (net (code "67") (name "Net-(U4-CS#)") (class "Default")
      (node (ref "R10") (pin "1") (pinfunction "1_1") (pintype "input"))
      (node (ref "R7") (pin "2") (pinfunction "2_2") (pintype "input"))
      (node (ref "U4") (pin "1") (pinfunction "CS#_1") (pintype "unspecified"))
    )
    (net (code "68") (name "Net-(U4-DI(IO0))") (class "Default")
      (node (ref "R15") (pin "1") (pinfunction "1_1") (pintype "input"))
      (node (ref "R16") (pin "1") (pinfunction "1_1") (pintype "input"))
      (node (ref "R17") (pin "1") (pinfunction "1_1") (pintype "input"))
      (node (ref "U4") (pin "5") (pinfunction "DI(IO0)_5") (pintype "unspecified"))
    )
    (net (code "69") (name "Net-(U4-DO(IO1))") (class "Default")
      (node (ref "R11") (pin "1") (pinfunction "1_1") (pintype "input"))
      (node (ref "R8") (pin "2") (pinfunction "2_2") (pintype "input"))
      (node (ref "U4") (pin "2") (pinfunction "DO(IO1)_2") (pintype "unspecified"))
    )
    (net (code "70") (name "Net-(U4-HOLD#_or_RESET#(IO3))") (class "Default")
      (node (ref "R13") (pin "1") (pinfunction "1_1") (pintype "input"))
      (node (ref "U4") (pin "7") (pinfunction "HOLD#_or_RESET#(IO3)_7") (pintype "unspecified"))
    )
    (net (code "71") (name "Net-(U4-VCC)") (class "Default")
      (node (ref "C20") (pin "2") (pinfunction "2_2") (pintype "unspecified"))
      (node (ref "U4") (pin "8") (pinfunction "VCC_8") (pintype "unspecified"))
    )
    (net (code "72") (name "Net-(U4-WP#(IO2))") (class "Default")
      (node (ref "R12") (pin "1") (pinfunction "1_1") (pintype "input"))
      (node (ref "R9") (pin "2") (pinfunction "2_2") (pintype "input"))
      (node (ref "U4") (pin "3") (pinfunction "WP#(IO2)_3") (pintype "unspecified"))
    )
    (net (code "73") (name "Net-(U5-CB)") (class "Default")
      (node (ref "C22") (pin "2") (pinfunction "2_2") (pintype "unspecified"))
      (node (ref "U5") (pin "6") (pinfunction "CB_6") (pintype "unspecified"))
    )
    (net (code "74") (name "Net-(U5-FB)") (class "Default")
      (node (ref "R19") (pin "1") (pinfunction "1_1") (pintype "input"))
      (node (ref "R20") (pin "2") (pinfunction "2_2") (pintype "input"))
      (node (ref "U5") (pin "4") (pinfunction "FB_4") (pintype "unspecified"))
    )
    (net (code "75") (name "Net-(U5-SW)") (class "Default")
      (node (ref "C22") (pin "1") (pinfunction "1_1") (pintype "unspecified"))
      (node (ref "L2") (pin "1") (pinfunction "1_1") (pintype "input"))
      (node (ref "U5") (pin "2") (pinfunction "SW_2") (pintype "unspecified"))
    )
    (net (code "76") (name "Net-(USB1-CC1)") (class "Default")
      (node (ref "R5") (pin "1") (pinfunction "1_1") (pintype "input"))
      (node (ref "USB1") (pin "A5") (pinfunction "CC1_A5") (pintype "unspecified"))
    )
    (net (code "77") (name "Net-(USB1-CC2)") (class "Default")
      (node (ref "R6") (pin "1") (pinfunction "1_1") (pintype "input"))
      (node (ref "USB1") (pin "B5") (pinfunction "CC2_B5") (pintype "unspecified"))
    )
    (net (code "78") (name "Net-(USB1-EH-Pad13)") (class "Default")
      (node (ref "USB1") (pin "13") (pinfunction "EH_13") (pintype "unspecified"))
      (node (ref "USB1") (pin "14") (pinfunction "EH_14") (pintype "unspecified"))
      (node (ref "USB1") (pin "A1B12") (pinfunction "GND_A1B12") (pintype "unspecified"))
      (node (ref "USB1") (pin "B1A12") (pinfunction "GND_B1A12") (pintype "unspecified"))
    )
    (net (code "79") (name "Net-(USB1-VBUS-PadA4B9)") (class "Default")
      (node (ref "USB1") (pin "A4B9") (pinfunction "VBUS_A4B9") (pintype "unspecified"))
      (node (ref "USB1") (pin "B4A9") (pinfunction "VBUS_B4A9") (pintype "unspecified"))
    )
    (net (code "80") (name "VCC") (class "Default")
      (node (ref "C10") (pin "2") (pinfunction "2_2") (pintype "unspecified"))
      (node (ref "C21") (pin "2") (pinfunction "2_2") (pintype "input"))
      (node (ref "C5") (pin "2") (pinfunction "2_2") (pintype "unspecified"))
      (node (ref "C6") (pin "2") (pinfunction "2_2") (pintype "unspecified"))
      (node (ref "C7") (pin "2") (pinfunction "2_2") (pintype "unspecified"))
      (node (ref "C8") (pin "2") (pinfunction "2_2") (pintype "unspecified"))
      (node (ref "C9") (pin "2") (pinfunction "2_2") (pintype "unspecified"))
      (node (ref "H1") (pin "11") (pinfunction "11_11") (pintype "unspecified"))
      (node (ref "H2") (pin "20") (pinfunction "20_20") (pintype "unspecified"))
      (node (ref "R1") (pin "2") (pinfunction "2_2") (pintype "input"))
      (node (ref "SW1") (pin "1") (pinfunction "1_1") (pintype "unspecified"))
      (node (ref "U1") (pin "1") (pinfunction "VBAT_1") (pintype "unspecified"))
      (node (ref "U1") (pin "19") (pinfunction "VDD_19") (pintype "unspecified"))
      (node (ref "U1") (pin "32") (pinfunction "VDD_32") (pintype "unspecified"))
      (node (ref "U1") (pin "48") (pinfunction "VDD_48") (pintype "unspecified"))
      (node (ref "U1") (pin "64") (pinfunction "VDD_64") (pintype "unspecified"))
      (node (ref "U2") (pin "1") (pinfunction "+_1") (pintype "unspecified"))
      (node (ref "U5") (pin "3") (pinfunction "VIN_3") (pintype "unspecified"))
      (node (ref "U5") (pin "5") (pinfunction "EN_5") (pintype "unspecified"))
    )
    (net (code "81") (name "VDDA") (class "Default")
      (node (ref "C13") (pin "2") (pinfunction "2_2") (pintype "unspecified"))
      (node (ref "C14") (pin "2") (pinfunction "2_2") (pintype "unspecified"))
      (node (ref "U1") (pin "13") (pinfunction "VDDA_13") (pintype "unspecified"))
    )
    (net (code "82") (name "unconnected-(CARD1-VDD-Pad4)") (class "Default")
      (node (ref "CARD1") (pin "4") (pinfunction "VDD_4") (pintype "unspecified"))
    )
    (net (code "83") (name "unconnected-(CARD1-VSS-Pad6)") (class "Default")
      (node (ref "CARD1") (pin "6") (pinfunction "VSS_6") (pintype "unspecified"))
    )
    (net (code "84") (name "unconnected-(U4-EP-Pad9)") (class "Default")
      (node (ref "U4") (pin "9") (pinfunction "EP_9") (pintype "unspecified"))
    )
    (net (code "85") (name "unconnected-(USB1-SBU1-PadA8)") (class "Default")
      (node (ref "USB1") (pin "A8") (pinfunction "SBU1_A8") (pintype "unspecified+no_connect"))
    )
    (net (code "86") (name "unconnected-(USB1-SBU2-PadB8)") (class "Default")
      (node (ref "USB1") (pin "B8") (pinfunction "SBU2_B8") (pintype "unspecified+no_connect"))
    )
  )
)
